# Power_Management.net
KiCad netlist of a schematic drawn in Altium Designer
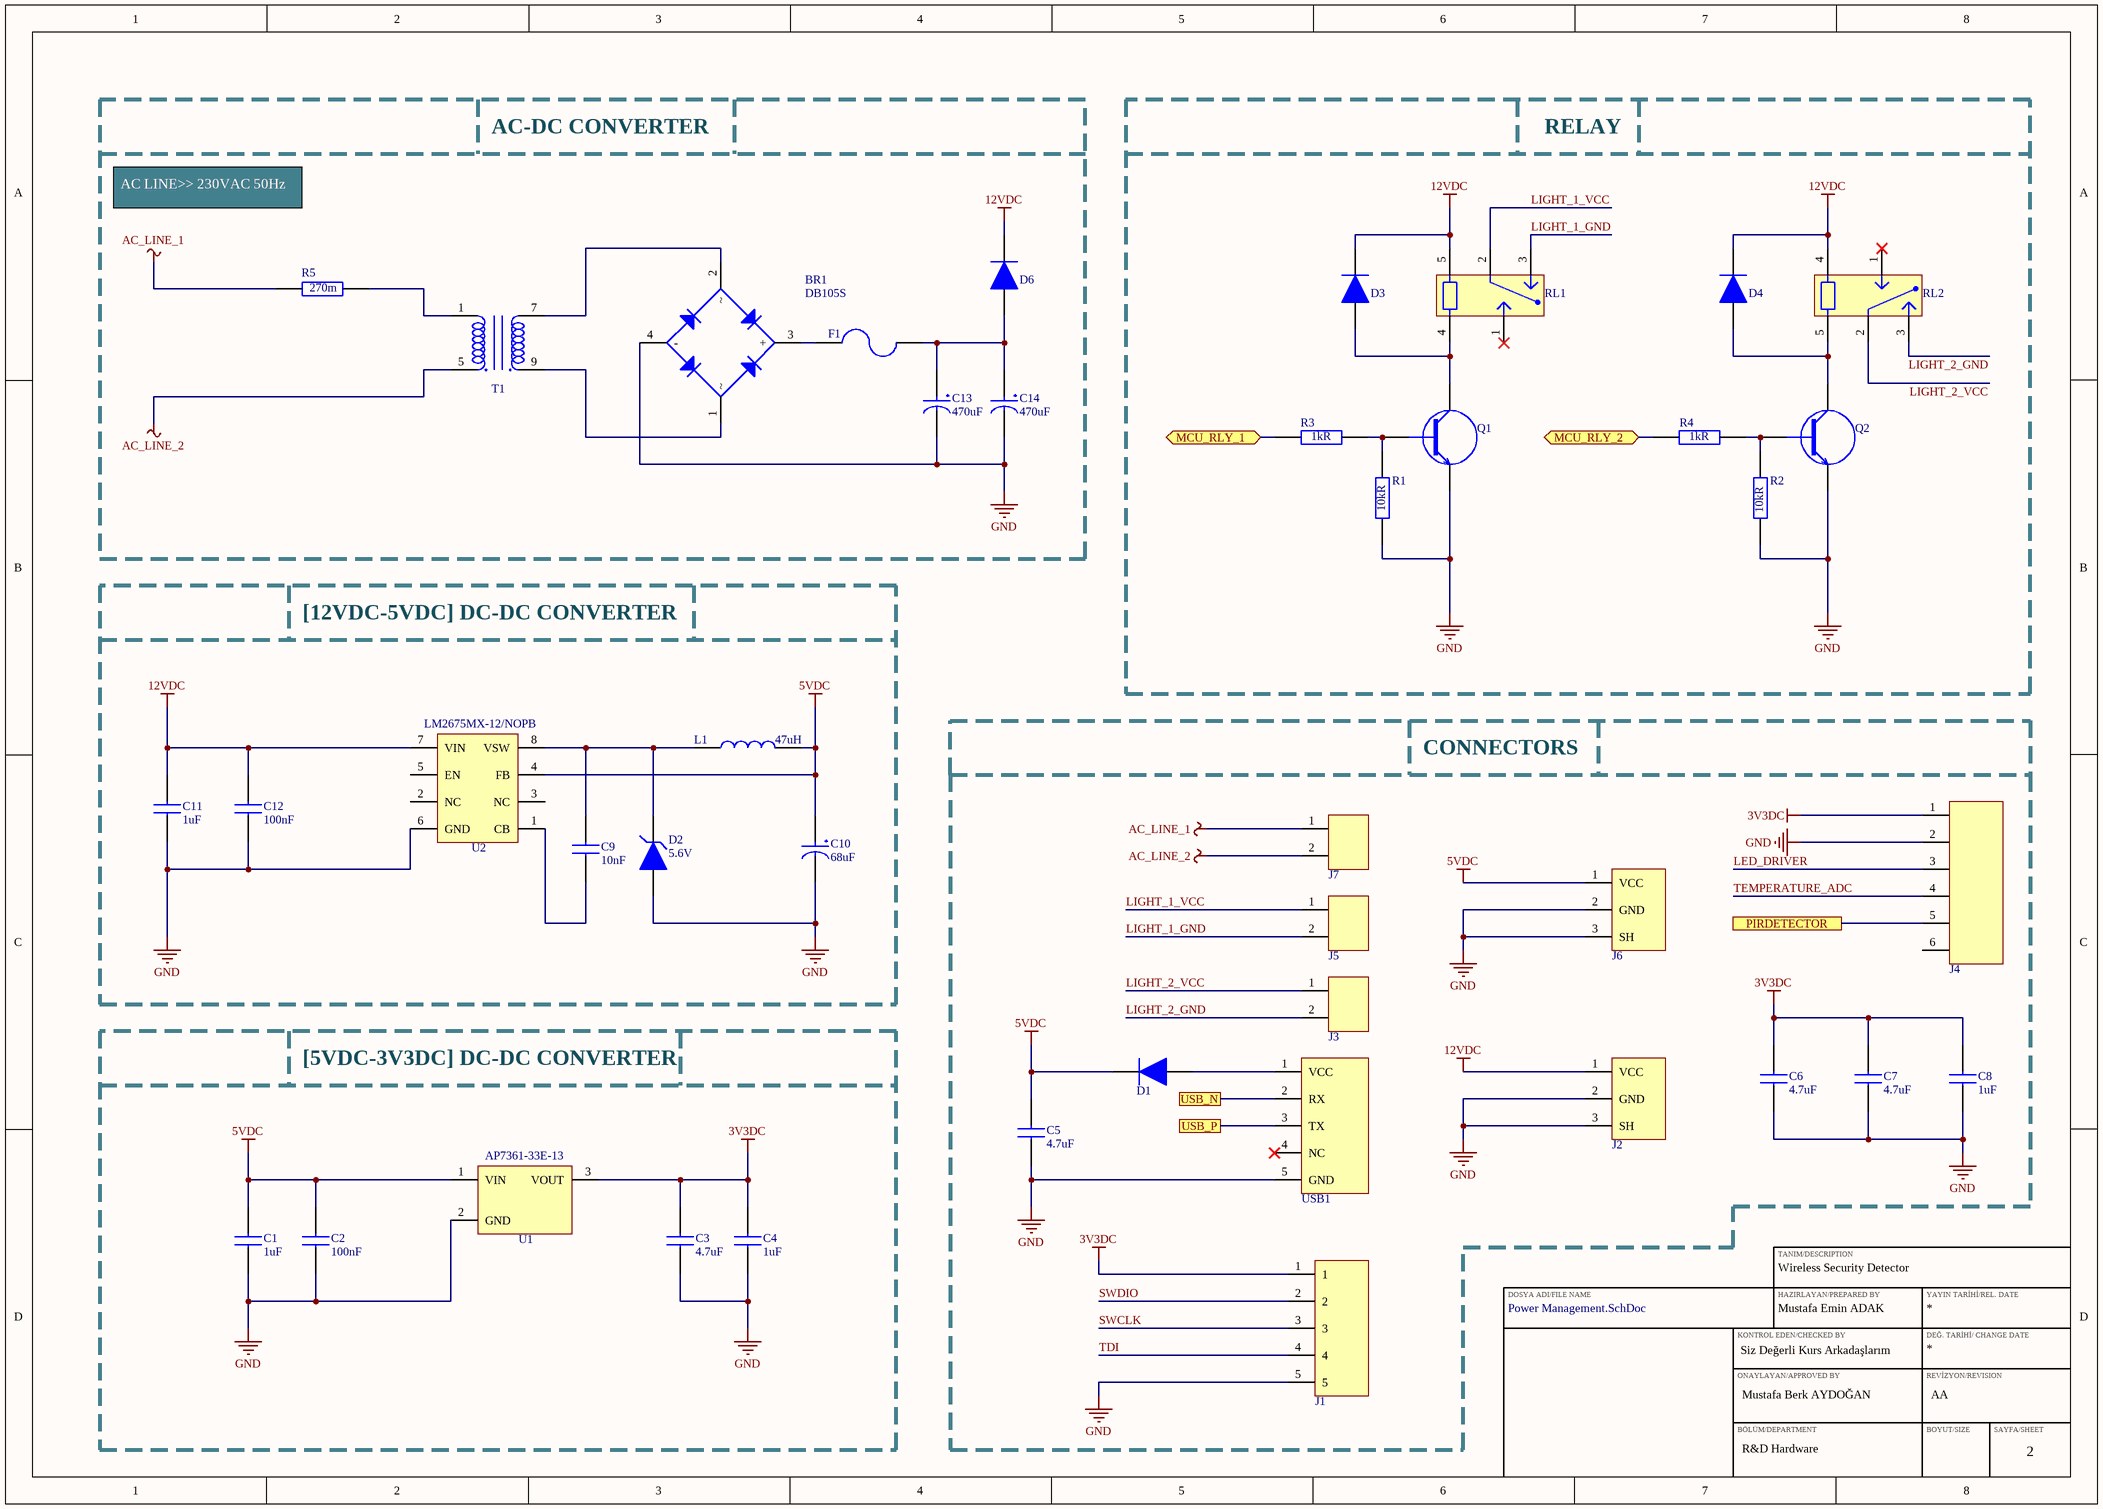
[diagram p0: Power Management.SchDoc]

(export (version "E")
  (design (tool "Eeschema 10.0.6"))
  (components
    (comp (ref "BR1")
      (value "DB105S")
      (footprint "DB105S")
      (description "¦Bridge Rectifier Single Phase Standard 600 V Surface Mount DB-S")
      (fields
        (field (name "MANUFACTURER") "SMC Diode Solutions")
        (field (name "VOLTAGE") "600V")
        (field (name "DESIGNED BY") "ADAK")
      )
      (libsource (lib "Udemy_ADAK_Library1") (part "DB105S"))
    )
    (comp (ref "C1")
      (value "CL21B105KBFNNNE")
      (footprint "CAP_0805")
      (description "¦CAP CER 1UF %10 0805 SMD X7R")
      (fields
        (field (name "MANUFACTURER") "Samsung")
        (field (name "TOLERANCE") "10%")
        (field (name "CAPACITANCE") "1uF")
        (field (name "DESIGNED BY") "ADAK")
      )
      (libsource (lib "Udemy_ADAK_Library1") (part "CAP CER 1uF 0805"))
    )
    (comp (ref "C2")
      (value "C0603C104K4RAC7867")
      (footprint "CAP_0603")
      (description "¦CAP CER 100nF (0.1UF) %10 0603 SMD")
      (fields
        (field (name "MANUFACTURER") "KEMET")
        (field (name "MANUFACTURER PART NUMBER") "C0603C104K4RACTU")
        (field (name "CAPACITANCE") "100nF")
        (field (name "DESIGNED BY") "ADAK")
      )
      (libsource (lib "Udemy_ADAK_Library1") (part "CAP CER 100nF 0603"))
    )
    (comp (ref "C3")
      (value "CL21A475KAQNNNE")
      (footprint "CAP_0805")
      (description "¦CAP CER 4.7UF %10 0805 SMD X5R")
      (fields
        (field (name "MANUFACTURER") "Samsung")
        (field (name "TOLERANCE") "10%")
        (field (name "CAPACITANCE") "4.7uF")
        (field (name "DESIGNED BY") "ADAK")
      )
      (libsource (lib "Udemy_ADAK_Library1") (part "CAP CER 4.7uF 0805"))
    )
    (comp (ref "C4")
      (value "CL21B105KBFNNNE")
      (footprint "CAP_0805")
      (description "¦CAP CER 1UF %10 0805 SMD X7R")
      (fields
        (field (name "MANUFACTURER") "Samsung")
        (field (name "TOLERANCE") "10%")
        (field (name "CAPACITANCE") "1uF")
        (field (name "DESIGNED BY") "ADAK")
      )
      (libsource (lib "Udemy_ADAK_Library1") (part "CAP CER 1uF 0805"))
    )
    (comp (ref "C5")
      (value "CL21A475KAQNNNE")
      (footprint "CAP_0805")
      (description "¦CAP CER 4.7UF %10 0805 SMD X5R")
      (fields
        (field (name "MANUFACTURER") "Samsung")
        (field (name "TOLERANCE") "10%")
        (field (name "CAPACITANCE") "4.7uF")
        (field (name "DESIGNED BY") "ADAK")
      )
      (libsource (lib "Udemy_ADAK_Library1") (part "CAP CER 4.7uF 0805"))
    )
    (comp (ref "C6")
      (value "CL21A475KAQNNNE")
      (footprint "CAP_0805")
      (description "¦CAP CER 4.7UF %10 0805 SMD X5R")
      (fields
        (field (name "MANUFACTURER") "Samsung")
        (field (name "TOLERANCE") "10%")
        (field (name "CAPACITANCE") "4.7uF")
        (field (name "DESIGNED BY") "ADAK")
      )
      (libsource (lib "Udemy_ADAK_Library1") (part "CAP CER 4.7uF 0805"))
    )
    (comp (ref "C7")
      (value "CL21A475KAQNNNE")
      (footprint "CAP_0805")
      (description "¦CAP CER 4.7UF %10 0805 SMD X5R")
      (fields
        (field (name "MANUFACTURER") "Samsung")
        (field (name "TOLERANCE") "10%")
        (field (name "CAPACITANCE") "4.7uF")
        (field (name "DESIGNED BY") "ADAK")
      )
      (libsource (lib "Udemy_ADAK_Library1") (part "CAP CER 4.7uF 0805"))
    )
    (comp (ref "C8")
      (value "CL21B105KBFNNNE")
      (footprint "CAP_0805")
      (description "¦CAP CER 1UF %10 0805 SMD X7R")
      (fields
        (field (name "MANUFACTURER") "Samsung")
        (field (name "TOLERANCE") "10%")
        (field (name "CAPACITANCE") "1uF")
        (field (name "DESIGNED BY") "ADAK")
      )
      (libsource (lib "Udemy_ADAK_Library1") (part "CAP CER 1uF 0805"))
    )
    (comp (ref "C9")
      (value "0603B103K160CT")
      (footprint "CAP_0603")
      (description "¦CAP CER 10nF %10 0603 SMD X7R")
      (fields
        (field (name "MANUFACTURER") "Walsin Technologies")
        (field (name "TOLERANCE") "10%")
        (field (name "CAPACITANCE") "10nF")
        (field (name "DESIGNED BY") "ADAK")
      )
      (libsource (lib "Udemy_ADAK_Library1") (part "CAP CER 10nF 0603"))
    )
    (comp (ref "C10")
      (value "EEV686M035A9HAA")
      (footprint "CAP_EEV/SERIES")
      (description "¦CAP ALUM 68UF 20% 35V SMD")
      (fields
        (field (name "MANUFACTURER") "KEMET")
        (field (name "TOLERANCE") "20%")
        (field (name "CAPACITANCE") "68uF")
        (field (name "DESIGNED BY") "ADAK")
      )
      (libsource (lib "Udemy_ADAK_Library1") (part "CAP ALU 68uF"))
    )
    (comp (ref "C11")
      (value "CL21B105KBFNNNE")
      (footprint "CAP_0805")
      (description "¦CAP CER 1UF %10 0805 SMD X7R")
      (fields
        (field (name "MANUFACTURER") "Samsung")
        (field (name "TOLERANCE") "10%")
        (field (name "CAPACITANCE") "1uF")
        (field (name "DESIGNED BY") "ADAK")
      )
      (libsource (lib "Udemy_ADAK_Library1") (part "CAP CER 1uF 0805"))
    )
    (comp (ref "C12")
      (value "CL21B104KBCNNNC")
      (footprint "CAP_0805")
      (description "¦CAP CER 0.1UF (100nF) %10 0805 SMD X7R")
      (fields
        (field (name "MANUFACTURER") "Samsung")
        (field (name "TOLERANCE") "10%")
        (field (name "CAPACITANCE") "100nF")
        (field (name "DESIGNED BY") "ADAK")
      )
      (libsource (lib "Udemy_ADAK_Library1") (part "CAP CER 100nF 0805"))
    )
    (comp (ref "C13")
      (value "ESH477M050AH4AA")
      (footprint "CAP_RADIAL_D10_P5")
      (description "¦CAP (AL) 470UF 20% 50V RADIAL")
      (fields
        (field (name "MANUFACTURER") "KEMET")
        (field (name "TOLERANCE") "20%")
        (field (name "CAPACITANCE") "470uF")
        (field (name "DESIGNED BY") "ADAK")
      )
      (libsource (lib "Udemy_ADAK_Library1") (part "CAP ALU ELEC 470uF 50V"))
    )
    (comp (ref "C14")
      (value "ESH477M050AH4AA")
      (footprint "CAP_RADIAL_D10_P5")
      (description "¦CAP (AL) 470UF 20% 50V RADIAL")
      (fields
        (field (name "MANUFACTURER") "KEMET")
        (field (name "TOLERANCE") "20%")
        (field (name "CAPACITANCE") "470uF")
        (field (name "DESIGNED BY") "ADAK")
      )
      (libsource (lib "Udemy_ADAK_Library1") (part "CAP ALU ELEC 470uF 50V"))
    )
    (comp (ref "D1")
      (value "1N4148WS")
      (footprint "SOD323F")
      (description "¦Diode 75 V 150mA Surface Mount SOD-323F")
      (fields
        (field (name "MANUFACTURER") "ON Semiconductor / Fairchild")
        (field (name "DESIGNED BY") "ADAK")
      )
      (libsource (lib "Udemy_ADAK_Library1") (part "1N4148WS"))
    )
    (comp (ref "D2")
      (value "1SMB5919BT3G")
      (footprint "SMB")
      (description "¦Zener Diode 5.6 V 3 W ±5% Surface Mount SMB")
      (fields
        (field (name "MANUFACTURER") "ON Semiconductor")
        (field (name "TOLERANCE") "5%")
        (field (name "WORKING VOLTAGE") "5.6V")
        (field (name "DESIGNED BY") "ADAK")
      )
      (libsource (lib "Udemy_ADAK_Library1") (part "1SMB5919BT3G"))
    )
    (comp (ref "D3")
      (value "1N4148WS")
      (footprint "SOD323F")
      (description "¦Diode 75 V 150mA Surface Mount SOD-323F")
      (fields
        (field (name "MANUFACTURER") "ON Semiconductor / Fairchild")
        (field (name "DESIGNED BY") "ADAK")
      )
      (libsource (lib "Udemy_ADAK_Library1") (part "1N4148WS"))
    )
    (comp (ref "D4")
      (value "1N4148WS")
      (footprint "SOD323F")
      (description "¦Diode 75 V 150mA Surface Mount SOD-323F")
      (fields
        (field (name "MANUFACTURER") "ON Semiconductor / Fairchild")
        (field (name "DESIGNED BY") "ADAK")
      )
      (libsource (lib "Udemy_ADAK_Library1") (part "1N4148WS"))
    )
    (comp (ref "D6")
      (value "1N4148WS")
      (footprint "SOD323F")
      (description "¦Diode 75 V 150mA Surface Mount SOD-323F")
      (fields
        (field (name "MANUFACTURER") "ON Semiconductor / Fairchild")
        (field (name "DESIGNED BY") "ADAK")
      )
      (libsource (lib "Udemy_ADAK_Library1") (part "1N4148WS"))
    )
    (comp (ref "F1")
      (value "3413.0216.22")
      (footprint "3413.0216.22")
      (description "¦FUSE Chip Fast Acting 1A 32V SMD Solder Pad 1206")
      (fields (field (name "MANUFACTURER") "Schurter") (field (name "DESIGNED BY") "ADAK"))
      (libsource (lib "Udemy_ADAK_Library1") (part "FUSE 3413.0216.22"))
    )
    (comp (ref "J1")
      (value "SMH-105-02-L-S")
      (footprint "PINHEADER1X5_RA")
      (description "¦Connector-5 Position Receptacle 0.100\" (2.54mm) Surface Mount, Right Angle Gold")
      (fields (field (name "MANUFACTURER") "Samtec") (field (name "DESIGNED BY") "ADAK"))
      (libsource (lib "Udemy_ADAK_Library1") (part "SMH-105-02-L-S"))
    )
    (comp (ref "J2")
      (value "PJ-037AH-SMT-TR")
      (footprint "JACK")
      (fields (field (name "MANUFACTURER") "CUI") (field (name "DESIGNED BY") "ADAK"))
      (libsource (lib "Udemy_ADAK_Library1") (part "PJ-037AH-SMT-TR"))
    )
    (comp (ref "J3")
      (value "TBP01R1-508-02BE")
      (footprint "TBP01R1-508")
      (fields (field (name "MANUFACTURER") "CUI Devices") (field (name "DESIGNED BY") "ADAK"))
      (libsource (lib "Udemy_ADAK_Library1") (part "TBP01R1-508-02BE"))
    )
    (comp (ref "J4")
      (value "64800611622")
      (footprint "64800611622")
      (description "¦Connector (1.50mm) 6 Pin Header Through Hole")
      (fields (field (name "MANUFACTURER") "Wurth Electronics") (field (name "DESIGNED BY") "ADAK"))
      (libsource (lib "Udemy_ADAK_Library1") (part "64800611622_CONN_6P"))
    )
    (comp (ref "J5")
      (value "TBP01R1-508-02BE")
      (footprint "TBP01R1-508")
      (fields (field (name "MANUFACTURER") "CUI Devices") (field (name "DESIGNED BY") "ADAK"))
      (libsource (lib "Udemy_ADAK_Library1") (part "TBP01R1-508-02BE"))
    )
    (comp (ref "J6")
      (value "PJ-037AH-SMT-TR")
      (footprint "JACK")
      (fields (field (name "MANUFACTURER") "CUI") (field (name "DESIGNED BY") "ADAK"))
      (libsource (lib "Udemy_ADAK_Library1") (part "PJ-037AH-SMT-TR"))
    )
    (comp (ref "J7")
      (value "TBP01R1-508-02BE")
      (footprint "TBP01R1-508")
      (fields (field (name "MANUFACTURER") "CUI Devices") (field (name "DESIGNED BY") "ADAK"))
      (libsource (lib "Udemy_ADAK_Library1") (part "TBP01R1-508-02BE"))
    )
    (comp (ref "L1")
      (value "78438335470")
      (footprint "IND_1212")
      (description "¦FIXED IND 47UH 390MA 2.3 OHM SMD")
      (fields
        (field (name "MANUFACTURER") "Wurth Electronics")
        (field (name "TOLERANCE") "30%")
        (field (name "INDUCTANCE") "47uH")
        (field (name "DESIGNED BY") "ADAK")
      )
      (libsource (lib "Udemy_ADAK_Library1") (part "IND 47uH"))
    )
    (comp (ref "Q1")
      (value "MMBT3904-7-F")
      (footprint "SOT-23F")
      (description "¦Bipolar (BJT) Transistor NPN 40 V 200 mA 300MHz 300 mW Surface Mount SOT-23-3")
      (fields (field (name "MANUFACTURER") "Diodes Zetex") (field (name "DESIGNED BY") "ADAK"))
      (libsource (lib "Udemy_ADAK_Library1") (part "MMBT3904-7-F"))
    )
    (comp (ref "Q2")
      (value "MMBT3904-7-F")
      (footprint "SOT-23F")
      (description "¦Bipolar (BJT) Transistor NPN 40 V 200 mA 300MHz 300 mW Surface Mount SOT-23-3")
      (fields (field (name "MANUFACTURER") "Diodes Zetex") (field (name "DESIGNED BY") "ADAK"))
      (libsource (lib "Udemy_ADAK_Library1") (part "MMBT3904-7-F"))
    )
    (comp (ref "R1")
      (value "RC0603FR-0710KL")
      (footprint "RES_0603")
      (description "¦RES 10KΩ 1% 0603 SMD")
      (fields
        (field (name "MANUFACTURER") "Yageo")
        (field (name "TOLERANCE") "1%")
        (field (name "RESISTANCE") "10kR")
        (field (name "DESIGNED BY") "ADAK")
      )
      (libsource (lib "Udemy_ADAK_Library1") (part "RES 10K OHM 0603"))
    )
    (comp (ref "R2")
      (value "RC0603FR-0710KL")
      (footprint "RES_0603")
      (description "¦RES 10KΩ 1% 0603 SMD")
      (fields
        (field (name "MANUFACTURER") "Yageo")
        (field (name "TOLERANCE") "1%")
        (field (name "RESISTANCE") "10kR")
        (field (name "DESIGNED BY") "ADAK")
      )
      (libsource (lib "Udemy_ADAK_Library1") (part "RES 10K OHM 0603"))
    )
    (comp (ref "R3")
      (value "RC0603FR-071KL")
      (footprint "RES_0603")
      (description "¦RES 1KΩ 1% 0603 SMD")
      (fields
        (field (name "MANUFACTURER") "Yageo")
        (field (name "TOLERANCE") "1%")
        (field (name "RESISTANCE") "1kR")
        (field (name "DESIGNED BY") "ADAK")
      )
      (libsource (lib "Udemy_ADAK_Library1") (part "RES 1K OHM 0603"))
    )
    (comp (ref "R4")
      (value "RC0603FR-071KL")
      (footprint "RES_0603")
      (description "¦RES 1KΩ 1% 0603 SMD")
      (fields
        (field (name "MANUFACTURER") "Yageo")
        (field (name "TOLERANCE") "1%")
        (field (name "RESISTANCE") "1kR")
        (field (name "DESIGNED BY") "ADAK")
      )
      (libsource (lib "Udemy_ADAK_Library1") (part "RES 1K OHM 0603"))
    )
    (comp (ref "R5")
      (value "5WD27")
      (footprint "RES_AXIAL_W")
      (description "¦RES 0.27Ω 5%  AXIAL")
      (fields
        (field (name "MANUFACTURER") "NTE Electronics, Inc")
        (field (name "RESISTANCE") "270m")
        (field (name "DESIGNED BY") "ADAK")
      )
      (libsource (lib "Udemy_ADAK_Library1") (part "5WD27"))
    )
    (comp (ref "RL1")
      (value "ALQ112")
      (footprint "ALQ112")
      (description "¦General Purpose Relay SPDT (1 Form C) 12VDC Coil Through Hole")
      (fields (field (name "MANUFACTURER") "Panasonic") (field (name "DESIGNED BY") "ADAK"))
      (libsource (lib "Udemy_ADAK_Library1") (part "ALQ112"))
    )
    (comp (ref "RL2")
      (value "ALQ112")
      (footprint "ALQ112")
      (description "¦General Purpose Relay SPDT (1 Form C) 12VDC Coil Through Hole")
      (fields (field (name "MANUFACTURER") "Panasonic") (field (name "DESIGNED BY") "ADAK"))
      (libsource (lib "") (part "ALQ112_1"))
    )
    (comp (ref "T1")
      (value "BV302S12010-ZU")
      (footprint "BV302S")
      (description "¦Trafo 230V 1VA Through Hole")
      (fields (field (name "DESIGNED BY") "ADAK"))
      (libsource (lib "Udemy_ADAK_Library1") (part "BV302S12010-ZU"))
    )
    (comp (ref "U1")
      (value "AP7361-33E-13")
      (footprint "SOT223")
      (description "¦Linear Voltage Regulator IC Positive Fixed 1 Output 1A SOT-223-3")
      (fields (field (name "MANUFACTURER") "Diodes") (field (name "DESIGNED BY") "ADAK"))
      (libsource (lib "Udemy_ADAK_Library1") (part "AP7361-33E-13"))
    )
    (comp (ref "U2")
      (value "LM2675MX-12/NOPB")
      (footprint "SOIC8")
      (description "¦Regulator IC Positive Fixed 12V 1 Output 1A 8-SOIC (0.154\", 3.90mm Width)")
      (fields (field (name "MANUFACTURER") "TI National Semiconductor") (field (name "DESIGNED BY") "ADAK"))
      (libsource (lib "Udemy_ADAK_Library1") (part "LM2675MX-12/NOPB"))
    )
    (comp (ref "USB1")
      (value "10118192-0001LF")
      (footprint "MICRO_B_USB")
      (description "¦USB - micro B USB 2.0 Receptacle Connector 5 Position Surface Mount, Right Angle")
      (fields (field (name "MANUFACTURER") "Amphenol ICC / FCI") (field (name "DESIGNED BY") "ADAK"))
      (libsource (lib "Udemy_ADAK_Library1") (part "Micro B USB Connector"))
    )
  )
  (nets
    (net (code "1") (name "/LED_DRIVER") (class "Default")
      (node (ref "J4") (pin "3") (pinfunction "3_3") (pintype "passive"))
    )
    (net (code "2") (name "/LIGHT_1_GND") (class "Default")
      (node (ref "J5") (pin "2") (pinfunction "2_2") (pintype "power_in"))
      (node (ref "RL1") (pin "3") (pinfunction "3_3") (pintype "passive"))
    )
    (net (code "3") (name "/LIGHT_1_VCC") (class "Default")
      (node (ref "J5") (pin "1") (pinfunction "1_1") (pintype "power_in"))
      (node (ref "RL1") (pin "2") (pinfunction "2_2") (pintype "passive"))
    )
    (net (code "4") (name "/LIGHT_2_GND") (class "Default")
      (node (ref "J3") (pin "2") (pinfunction "2_2") (pintype "power_in"))
      (node (ref "RL2") (pin "3") (pinfunction "3_3") (pintype "passive"))
    )
    (net (code "5") (name "/LIGHT_2_VCC") (class "Default")
      (node (ref "J3") (pin "1") (pinfunction "1_1") (pintype "power_in"))
      (node (ref "RL2") (pin "2") (pinfunction "2_2") (pintype "passive"))
    )
    (net (code "6") (name "/MCU_RLY_1") (class "Default")
      (node (ref "R3") (pin "1") (pinfunction "1_1") (pintype "passive"))
    )
    (net (code "7") (name "/MCU_RLY_2") (class "Default")
      (node (ref "R4") (pin "1") (pinfunction "1_1") (pintype "passive"))
    )
    (net (code "8") (name "/PIRDETECTOR") (class "Default")
      (node (ref "J4") (pin "5") (pinfunction "5_5") (pintype "passive"))
    )
    (net (code "9") (name "/SWCLK") (class "Default")
      (node (ref "J1") (pin "3") (pinfunction "3_3") (pintype "passive"))
    )
    (net (code "10") (name "/SWDIO") (class "Default")
      (node (ref "J1") (pin "2") (pinfunction "2_2") (pintype "passive"))
    )
    (net (code "11") (name "/TDI") (class "Default")
      (node (ref "J1") (pin "4") (pinfunction "4_4") (pintype "passive"))
    )
    (net (code "12") (name "/TEMPERATURE_ADC") (class "Default")
      (node (ref "J4") (pin "4") (pinfunction "4_4") (pintype "passive"))
    )
    (net (code "13") (name "/USB_N") (class "Default")
      (node (ref "USB1") (pin "2") (pinfunction "RX_2") (pintype "passive"))
    )
    (net (code "14") (name "/USB_P") (class "Default")
      (node (ref "USB1") (pin "3") (pinfunction "TX_3") (pintype "passive"))
    )
    (net (code "15") (name "3V3DC") (class "Default")
      (node (ref "C3") (pin "2") (pinfunction "2_2") (pintype "passive"))
      (node (ref "C4") (pin "2") (pinfunction "2_2") (pintype "passive"))
      (node (ref "C6") (pin "2") (pinfunction "2_2") (pintype "passive"))
      (node (ref "C7") (pin "2") (pinfunction "2_2") (pintype "passive"))
      (node (ref "C8") (pin "2") (pinfunction "2_2") (pintype "passive"))
      (node (ref "J1") (pin "1") (pinfunction "1_1") (pintype "passive"))
      (node (ref "J4") (pin "1") (pinfunction "1_1") (pintype "passive"))
      (node (ref "U1") (pin "3") (pinfunction "VOUT_3") (pintype "passive"))
    )
    (net (code "16") (name "5VDC") (class "Default")
      (node (ref "C1") (pin "2") (pinfunction "2_2") (pintype "passive"))
      (node (ref "C10") (pin "1") (pinfunction "1_1") (pintype "passive"))
      (node (ref "C2") (pin "2") (pinfunction "2_2") (pintype "passive"))
      (node (ref "C5") (pin "2") (pinfunction "2_2") (pintype "passive"))
      (node (ref "D1") (pin "1") (pinfunction "1_1") (pintype "passive"))
      (node (ref "J6") (pin "1") (pinfunction "VCC_1") (pintype "power_in"))
      (node (ref "L1") (pin "2") (pinfunction "2_2") (pintype "passive"))
      (node (ref "U1") (pin "1") (pinfunction "VIN_1") (pintype "passive"))
      (node (ref "U2") (pin "4") (pinfunction "FB_4") (pintype "passive"))
    )
    (net (code "17") (name "12VDC") (class "Default")
      (node (ref "C11") (pin "2") (pinfunction "2_2") (pintype "passive"))
      (node (ref "C12") (pin "2") (pinfunction "2_2") (pintype "passive"))
      (node (ref "D3") (pin "1") (pinfunction "1_1") (pintype "passive"))
      (node (ref "D4") (pin "1") (pinfunction "1_1") (pintype "passive"))
      (node (ref "D6") (pin "1") (pinfunction "1_1") (pintype "passive"))
      (node (ref "J2") (pin "1") (pinfunction "VCC_1") (pintype "power_in"))
      (node (ref "RL1") (pin "5") (pinfunction "5_5") (pintype "passive"))
      (node (ref "RL2") (pin "4") (pinfunction "4_4") (pintype "passive"))
      (node (ref "U2") (pin "7") (pinfunction "VIN_7") (pintype "passive"))
    )
    (net (code "18") (name "AC_LINE_1") (class "Default")
      (node (ref "J7") (pin "1") (pinfunction "1_1") (pintype "power_in"))
      (node (ref "R5") (pin "1") (pinfunction "1_1") (pintype "passive"))
    )
    (net (code "19") (name "AC_LINE_2") (class "Default")
      (node (ref "J7") (pin "2") (pinfunction "2_2") (pintype "power_in"))
      (node (ref "T1") (pin "5") (pinfunction "5_5") (pintype "passive"))
    )
    (net (code "20") (name "GND") (class "Default")
      (node (ref "BR1") (pin "4") (pinfunction "-_4") (pintype "passive"))
      (node (ref "C1") (pin "1") (pinfunction "1_1") (pintype "passive"))
      (node (ref "C10") (pin "2") (pinfunction "2_2") (pintype "passive"))
      (node (ref "C11") (pin "1") (pinfunction "1_1") (pintype "passive"))
      (node (ref "C12") (pin "1") (pinfunction "1_1") (pintype "passive"))
      (node (ref "C13") (pin "2") (pinfunction "2_2") (pintype "passive"))
      (node (ref "C14") (pin "2") (pinfunction "2_2") (pintype "passive"))
      (node (ref "C2") (pin "1") (pinfunction "1_1") (pintype "passive"))
      (node (ref "C3") (pin "1") (pinfunction "1_1") (pintype "passive"))
      (node (ref "C4") (pin "1") (pinfunction "1_1") (pintype "passive"))
      (node (ref "C5") (pin "1") (pinfunction "1_1") (pintype "passive"))
      (node (ref "C6") (pin "1") (pinfunction "1_1") (pintype "passive"))
      (node (ref "C7") (pin "1") (pinfunction "1_1") (pintype "passive"))
      (node (ref "C8") (pin "1") (pinfunction "1_1") (pintype "passive"))
      (node (ref "D2") (pin "C") (pinfunction "C_C") (pintype "passive"))
      (node (ref "J1") (pin "5") (pinfunction "5_5") (pintype "passive"))
      (node (ref "J2") (pin "2") (pinfunction "GND_2") (pintype "power_in"))
      (node (ref "J2") (pin "3") (pinfunction "SH_3") (pintype "power_in"))
      (node (ref "J4") (pin "2") (pinfunction "2_2") (pintype "passive"))
      (node (ref "J6") (pin "2") (pinfunction "GND_2") (pintype "power_in"))
      (node (ref "J6") (pin "3") (pinfunction "SH_3") (pintype "power_in"))
      (node (ref "Q1") (pin "2") (pinfunction "E_2") (pintype "passive"))
      (node (ref "Q2") (pin "2") (pinfunction "E_2") (pintype "passive"))
      (node (ref "R1") (pin "1") (pinfunction "1_1") (pintype "passive"))
      (node (ref "R2") (pin "1") (pinfunction "1_1") (pintype "passive"))
      (node (ref "U1") (pin "2") (pinfunction "GND_2") (pintype "passive"))
      (node (ref "U2") (pin "6") (pinfunction "GND_6") (pintype "passive"))
      (node (ref "USB1") (pin "5") (pinfunction "GND_5") (pintype "passive"))
    )
    (net (code "21") (name "Net-(BR1-+)") (class "Default")
      (node (ref "BR1") (pin "3") (pinfunction "+_3") (pintype "passive"))
      (node (ref "F1") (pin "1") (pinfunction "1_1") (pintype "passive"))
    )
    (net (code "22") (name "Net-(BR1-~-Pad1)") (class "Default")
      (node (ref "BR1") (pin "1") (pinfunction "~_1") (pintype "passive"))
      (node (ref "T1") (pin "9") (pinfunction "9_9") (pintype "passive"))
    )
    (net (code "23") (name "Net-(BR1-~-Pad2)") (class "Default")
      (node (ref "BR1") (pin "2") (pinfunction "~_2") (pintype "passive"))
      (node (ref "T1") (pin "7") (pinfunction "7_7") (pintype "passive"))
    )
    (net (code "24") (name "Net-(C13-Pad1)") (class "Default")
      (node (ref "C13") (pin "1") (pinfunction "1_1") (pintype "passive"))
      (node (ref "C14") (pin "1") (pinfunction "1_1") (pintype "passive"))
      (node (ref "D6") (pin "2") (pinfunction "2_2") (pintype "passive"))
      (node (ref "F1") (pin "2") (pinfunction "2_2") (pintype "passive"))
    )
    (net (code "25") (name "Net-(Q1-B)") (class "Default")
      (node (ref "Q1") (pin "1") (pinfunction "B_1") (pintype "passive"))
      (node (ref "R1") (pin "2") (pinfunction "2_2") (pintype "passive"))
      (node (ref "R3") (pin "2") (pinfunction "2_2") (pintype "passive"))
    )
    (net (code "26") (name "Net-(Q1-C)") (class "Default")
      (node (ref "D3") (pin "2") (pinfunction "2_2") (pintype "passive"))
      (node (ref "Q1") (pin "3") (pinfunction "C_3") (pintype "passive"))
      (node (ref "RL1") (pin "4") (pinfunction "4_4") (pintype "passive"))
    )
    (net (code "27") (name "Net-(Q2-B)") (class "Default")
      (node (ref "Q2") (pin "1") (pinfunction "B_1") (pintype "passive"))
      (node (ref "R2") (pin "2") (pinfunction "2_2") (pintype "passive"))
      (node (ref "R4") (pin "2") (pinfunction "2_2") (pintype "passive"))
    )
    (net (code "28") (name "Net-(Q2-C)") (class "Default")
      (node (ref "D4") (pin "2") (pinfunction "2_2") (pintype "passive"))
      (node (ref "Q2") (pin "3") (pinfunction "C_3") (pintype "passive"))
      (node (ref "RL2") (pin "5") (pinfunction "5_5") (pintype "passive"))
    )
    (net (code "29") (name "Net-(R5-Pad2)") (class "Default")
      (node (ref "R5") (pin "2") (pinfunction "2_2") (pintype "passive"))
      (node (ref "T1") (pin "1") (pinfunction "1_1") (pintype "passive"))
    )
    (net (code "30") (name "Net-(U2-CB)") (class "Default")
      (node (ref "C9") (pin "1") (pinfunction "1_1") (pintype "passive"))
      (node (ref "U2") (pin "1") (pinfunction "CB_1") (pintype "passive"))
    )
    (net (code "31") (name "Net-(U2-VSW)") (class "Default")
      (node (ref "C9") (pin "2") (pinfunction "2_2") (pintype "passive"))
      (node (ref "D2") (pin "A") (pinfunction "A_A") (pintype "passive"))
      (node (ref "L1") (pin "1") (pinfunction "1_1") (pintype "passive"))
      (node (ref "U2") (pin "8") (pinfunction "VSW_8") (pintype "passive"))
    )
    (net (code "32") (name "Net-(USB1-VCC)") (class "Default")
      (node (ref "D1") (pin "2") (pinfunction "2_2") (pintype "passive"))
      (node (ref "USB1") (pin "1") (pinfunction "VCC_1") (pintype "passive"))
    )
    (net (code "33") (name "unconnected-(J4-Pad6)") (class "Default")
      (node (ref "J4") (pin "6") (pinfunction "6_6") (pintype "passive"))
    )
    (net (code "34") (name "unconnected-(RL1-Pad1)") (class "Default")
      (node (ref "RL1") (pin "1") (pinfunction "1_1") (pintype "passive+no_connect"))
    )
    (net (code "35") (name "unconnected-(RL2-Pad1)") (class "Default")
      (node (ref "RL2") (pin "1") (pinfunction "1_1") (pintype "passive+no_connect"))
    )
    (net (code "36") (name "unconnected-(U2-EN-Pad5)") (class "Default")
      (node (ref "U2") (pin "5") (pinfunction "EN_5") (pintype "passive"))
    )
    (net (code "37") (name "unconnected-(U2-NC-Pad2)") (class "Default")
      (node (ref "U2") (pin "2") (pinfunction "NC_2") (pintype "passive"))
    )
    (net (code "38") (name "unconnected-(U2-NC-Pad3)") (class "Default")
      (node (ref "U2") (pin "3") (pinfunction "NC_3") (pintype "passive"))
    )
    (net (code "39") (name "unconnected-(USB1-NC-Pad4)") (class "Default")
      (node (ref "USB1") (pin "4") (pinfunction "NC_4") (pintype "passive+no_connect"))
    )
  )
)
